# IrrigationControl.net
KiCad netlist of a schematic drawn in EAGLE
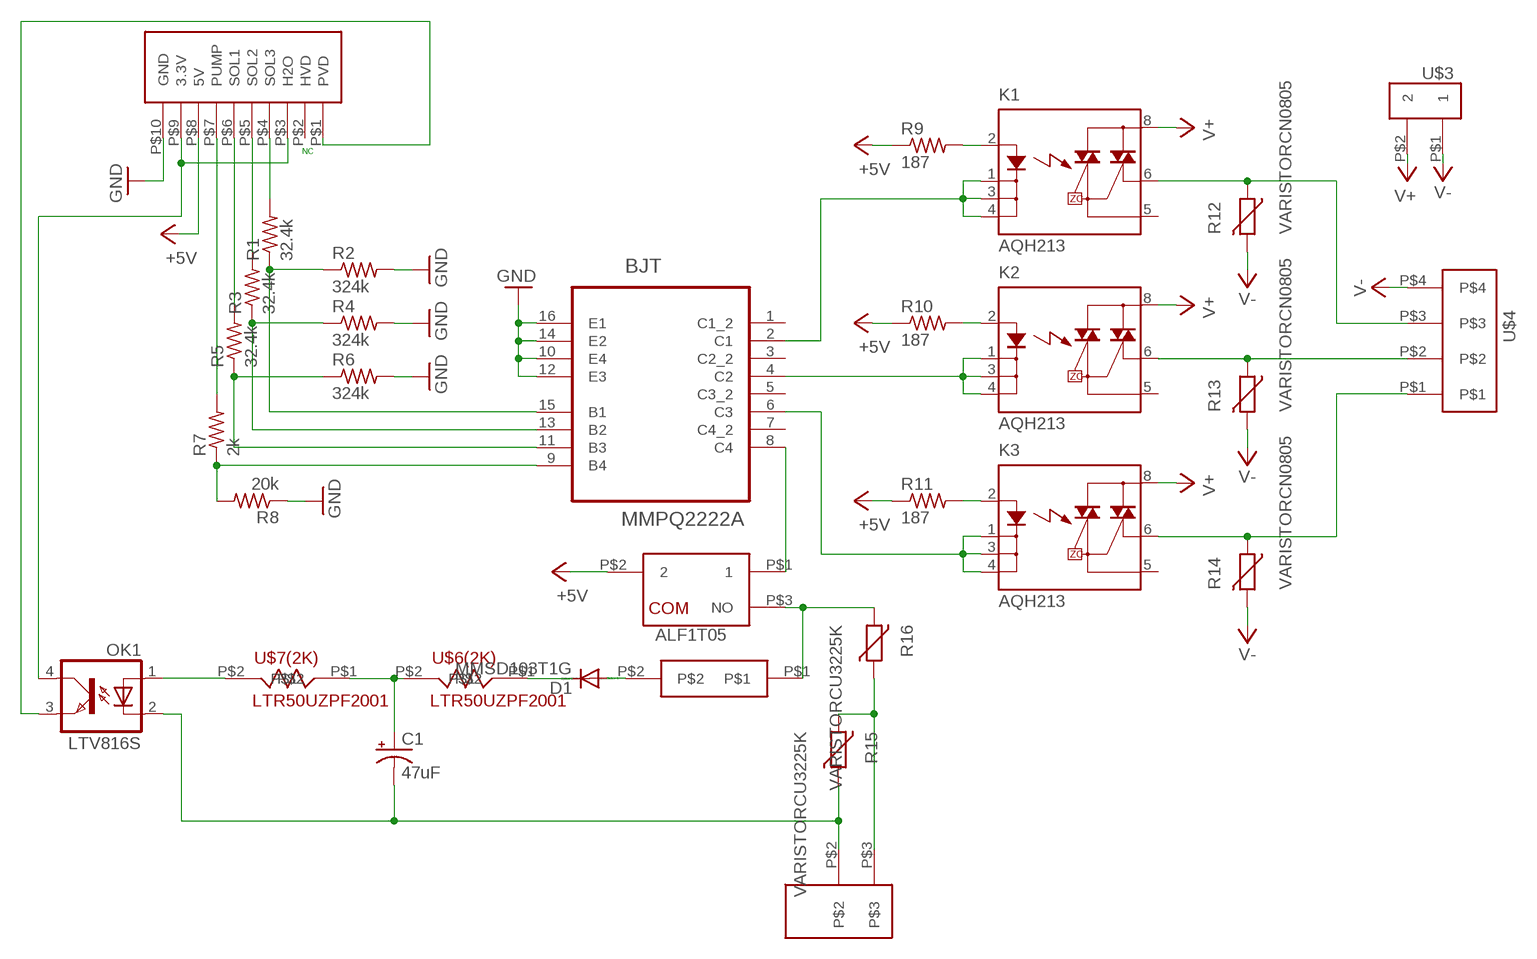
[diagram p0: schematic, sheet 1]

(export (version "E")
  (design (tool "Eeschema 10.0.6"))
  (components
    (comp (ref "ALF1T05")
      (value "ALF1T05")
      (footprint "eagle-import:TMP")
      (libsource (lib "eagle-import") (part "ALF1T05"))
    )
    (comp (ref "BJT")
      (value "MMPQ2222A")
      (footprint "eagle-import:SOIC127P600X175-16N")
      (libsource (lib "eagle-import") (part "MMPQ2222A"))
    )
    (comp (ref "C1")
      (value "47uF")
      (footprint "eagle-import:E5-10,5")
      (libsource (lib "eagle-import") (part "CPOL-USE5-10.5"))
    )
    (comp (ref "D1")
      (value "MMSD103T1G")
      (footprint "eagle-import:SOD123")
      (libsource (lib "eagle-import") (part "DIODE-SOD123"))
    )
    (comp (ref "K1")
      (value "AQH213")
      (footprint "eagle-import:DIL07")
      (libsource (lib "eagle-import") (part "AQH213"))
    )
    (comp (ref "K2")
      (value "AQH213")
      (footprint "eagle-import:DIL07")
      (libsource (lib "eagle-import") (part "AQH213"))
    )
    (comp (ref "K3")
      (value "AQH213")
      (footprint "eagle-import:DIL07")
      (libsource (lib "eagle-import") (part "AQH213"))
    )
    (comp (ref "OK1")
      (value "LTV816S")
      (footprint "eagle-import:SMD4")
      (libsource (lib "eagle-import") (part "LTV816S"))
    )
    (comp (ref "R1")
      (value "32.4k")
      (footprint "eagle-import:R0805")
      (libsource (lib "eagle-import") (part "R-US_R0805"))
    )
    (comp (ref "R2")
      (value "324k")
      (footprint "eagle-import:R0805")
      (libsource (lib "eagle-import") (part "R-US_R0805"))
    )
    (comp (ref "R3")
      (value "32.4k")
      (footprint "eagle-import:R0805")
      (libsource (lib "eagle-import") (part "R-US_R0805"))
    )
    (comp (ref "R4")
      (value "324k")
      (footprint "eagle-import:R0805")
      (libsource (lib "eagle-import") (part "R-US_R0805"))
    )
    (comp (ref "R5")
      (value "32.4k")
      (footprint "eagle-import:R0805")
      (libsource (lib "eagle-import") (part "R-US_R0805"))
    )
    (comp (ref "R6")
      (value "324k")
      (footprint "eagle-import:R0805")
      (libsource (lib "eagle-import") (part "R-US_R0805"))
    )
    (comp (ref "R7")
      (value "2k")
      (footprint "eagle-import:R0805")
      (libsource (lib "eagle-import") (part "R-US_R0805"))
    )
    (comp (ref "R8")
      (value "20k")
      (footprint "eagle-import:R0805")
      (libsource (lib "eagle-import") (part "R-US_R0805"))
    )
    (comp (ref "R9")
      (value "187")
      (footprint "eagle-import:R0805")
      (libsource (lib "eagle-import") (part "R-US_R0805"))
    )
    (comp (ref "R10")
      (value "187")
      (footprint "eagle-import:R0805")
      (libsource (lib "eagle-import") (part "R-US_R0805"))
    )
    (comp (ref "R11")
      (value "187")
      (footprint "eagle-import:R0805")
      (libsource (lib "eagle-import") (part "R-US_R0805"))
    )
    (comp (ref "R12")
      (value "VARISTORCN0805")
      (footprint "eagle-import:CT_CN0805")
      (libsource (lib "eagle-import") (part "VARISTORCN0805"))
    )
    (comp (ref "R13")
      (value "VARISTORCN0805")
      (footprint "eagle-import:CT_CN0805")
      (libsource (lib "eagle-import") (part "VARISTORCN0805"))
    )
    (comp (ref "R14")
      (value "VARISTORCN0805")
      (footprint "eagle-import:CT_CN0805")
      (libsource (lib "eagle-import") (part "VARISTORCN0805"))
    )
    (comp (ref "R15")
      (value "VARISTORCU3225K")
      (footprint "eagle-import:CU3225K")
      (libsource (lib "eagle-import") (part "VARISTORCU3225K"))
    )
    (comp (ref "R16")
      (value "VARISTORCU3225K")
      (footprint "eagle-import:CU3225K")
      (libsource (lib "eagle-import") (part "VARISTORCU3225K"))
    )
    (comp (ref "U$1")
      (value "OSTT7030150")
      (footprint "eagle-import:OSTT7030150")
      (libsource (lib "eagle-import") (part "OSTT7030150"))
    )
    (comp (ref "U$2")
      (value "OSTTE100104")
      (footprint "eagle-import:OSTTE100104")
      (libsource (lib "eagle-import") (part "OSTTE100104"))
    )
    (comp (ref "U$3")
      (value "OSTTC020162")
      (footprint "eagle-import:OSTTC020162")
      (libsource (lib "eagle-import") (part "OSTTC020162"))
    )
    (comp (ref "U$4")
      (value "OSTTE040104")
      (footprint "eagle-import:OSTTEX040104")
      (libsource (lib "eagle-import") (part "OSTTE040104"))
    )
    (comp (ref "U$5")
      (value "SST-357")
      (footprint "eagle-import:SST")
      (libsource (lib "eagle-import") (part "SST-357"))
    )
    (comp (ref "U$6(2K)")
      (value "LTR50UZPF2001")
      (footprint "eagle-import:WIDE2010")
      (libsource (lib "eagle-import") (part "LTR50UZPF2001"))
    )
    (comp (ref "U$7(2K)")
      (value "LTR50UZPF2001")
      (footprint "eagle-import:WIDE2010")
      (libsource (lib "eagle-import") (part "LTR50UZPF2001"))
    )
  )
  (nets
    (net (code "1") (name "+5V") (class "Default")
      (node (ref "ALF1T05") (pin "P$2") (pinfunction "2_P$2") (pintype "bidirectional"))
      (node (ref "R10") (pin "1") (pinfunction "1_1") (pintype "passive"))
      (node (ref "R11") (pin "1") (pinfunction "1_1") (pintype "passive"))
      (node (ref "R9") (pin "1") (pinfunction "1_1") (pintype "passive"))
      (node (ref "U$2") (pin "P$8") (pinfunction "5V_P$8") (pintype "power_in"))
    )
    (net (code "2") (name "GND") (class "Default")
      (node (ref "BJT") (pin "10") (pinfunction "E4_10") (pintype "passive"))
      (node (ref "BJT") (pin "12") (pinfunction "E3_12") (pintype "passive"))
      (node (ref "BJT") (pin "14") (pinfunction "E2_14") (pintype "passive"))
      (node (ref "BJT") (pin "16") (pinfunction "E1_16") (pintype "passive"))
      (node (ref "R2") (pin "2") (pinfunction "2_2") (pintype "passive"))
      (node (ref "R4") (pin "2") (pinfunction "2_2") (pintype "passive"))
      (node (ref "R6") (pin "2") (pinfunction "2_2") (pintype "passive"))
      (node (ref "R8") (pin "1") (pinfunction "1_1") (pintype "passive"))
      (node (ref "U$2") (pin "P$10") (pinfunction "GND_P$10") (pintype "bidirectional"))
    )
    (net (code "3") (name "Net-(ALF1T05-1)") (class "Default")
      (node (ref "ALF1T05") (pin "P$1") (pinfunction "1_P$1") (pintype "bidirectional"))
      (node (ref "BJT") (pin "8") (pinfunction "C4_8") (pintype "passive"))
    )
    (net (code "4") (name "Net-(ALF1T05-NO)") (class "Default")
      (node (ref "ALF1T05") (pin "P$3") (pinfunction "NO_P$3") (pintype "bidirectional"))
      (node (ref "R16") (pin "2") (pinfunction "2_2") (pintype "passive"))
      (node (ref "U$5") (pin "P$1") (pinfunction "P$1_P$1") (pintype "bidirectional"))
    )
    (net (code "5") (name "Net-(BJT-B1)") (class "Default")
      (node (ref "BJT") (pin "15") (pinfunction "B1_15") (pintype "passive"))
      (node (ref "R1") (pin "1") (pinfunction "1_1") (pintype "passive"))
      (node (ref "R2") (pin "1") (pinfunction "1_1") (pintype "passive"))
    )
    (net (code "6") (name "Net-(BJT-B2)") (class "Default")
      (node (ref "BJT") (pin "13") (pinfunction "B2_13") (pintype "passive"))
      (node (ref "R3") (pin "1") (pinfunction "1_1") (pintype "passive"))
      (node (ref "R4") (pin "1") (pinfunction "1_1") (pintype "passive"))
    )
    (net (code "7") (name "Net-(BJT-B3)") (class "Default")
      (node (ref "BJT") (pin "11") (pinfunction "B3_11") (pintype "passive"))
      (node (ref "R5") (pin "1") (pinfunction "1_1") (pintype "passive"))
      (node (ref "R6") (pin "1") (pinfunction "1_1") (pintype "passive"))
    )
    (net (code "8") (name "Net-(BJT-B4)") (class "Default")
      (node (ref "BJT") (pin "9") (pinfunction "B4_9") (pintype "passive"))
      (node (ref "R7") (pin "1") (pinfunction "1_1") (pintype "passive"))
      (node (ref "R8") (pin "2") (pinfunction "2_2") (pintype "passive"))
    )
    (net (code "9") (name "Net-(BJT-C1)") (class "Default")
      (node (ref "BJT") (pin "2") (pinfunction "C1_2") (pintype "passive"))
      (node (ref "K1") (pin "1") (pinfunction "K_1") (pintype "passive"))
      (node (ref "K1") (pin "3") (pinfunction "K1_3") (pintype "passive"))
      (node (ref "K1") (pin "4") (pinfunction "K2_4") (pintype "passive"))
    )
    (net (code "10") (name "Net-(BJT-C2)") (class "Default")
      (node (ref "BJT") (pin "4") (pinfunction "C2_4") (pintype "passive"))
      (node (ref "K2") (pin "1") (pinfunction "K_1") (pintype "passive"))
      (node (ref "K2") (pin "3") (pinfunction "K1_3") (pintype "passive"))
      (node (ref "K2") (pin "4") (pinfunction "K2_4") (pintype "passive"))
    )
    (net (code "11") (name "Net-(BJT-C3)") (class "Default")
      (node (ref "BJT") (pin "6") (pinfunction "C3_6") (pintype "passive"))
      (node (ref "K3") (pin "1") (pinfunction "K_1") (pintype "passive"))
      (node (ref "K3") (pin "3") (pinfunction "K1_3") (pintype "passive"))
      (node (ref "K3") (pin "4") (pinfunction "K2_4") (pintype "passive"))
    )
    (net (code "12") (name "Net-(C1-Pad+)") (class "Default")
      (node (ref "C1") (pin "+") (pinfunction "+_+") (pintype "passive"))
      (node (ref "U$6(2K)") (pin "P$2") (pinfunction "P$2_P$2") (pintype "bidirectional"))
      (node (ref "U$7(2K)") (pin "P$1") (pinfunction "P$1_P$1") (pintype "bidirectional"))
    )
    (net (code "13") (name "Net-(D1-PadA)") (class "Default")
      (node (ref "D1") (pin "A") (pinfunction "A_A") (pintype "passive"))
      (node (ref "U$5") (pin "P$2") (pinfunction "P$2_P$2") (pintype "bidirectional"))
    )
    (net (code "14") (name "Net-(D1-PadC)") (class "Default")
      (node (ref "D1") (pin "C") (pinfunction "C_C") (pintype "passive"))
      (node (ref "U$6(2K)") (pin "P$1") (pinfunction "P$1_P$1") (pintype "bidirectional"))
    )
    (net (code "15") (name "Net-(K1-A)") (class "Default")
      (node (ref "K1") (pin "2") (pinfunction "A_2") (pintype "passive"))
      (node (ref "R9") (pin "2") (pinfunction "2_2") (pintype "passive"))
    )
    (net (code "16") (name "Net-(K1-DS3)") (class "Default")
      (node (ref "K1") (pin "6") (pinfunction "DS3_6") (pintype "passive"))
      (node (ref "R12") (pin "1") (pinfunction "1_1") (pintype "passive"))
      (node (ref "U$4") (pin "P$3") (pinfunction "P$3_P$3") (pintype "bidirectional"))
    )
    (net (code "17") (name "Net-(K2-A)") (class "Default")
      (node (ref "K2") (pin "2") (pinfunction "A_2") (pintype "passive"))
      (node (ref "R10") (pin "2") (pinfunction "2_2") (pintype "passive"))
    )
    (net (code "18") (name "Net-(K2-DS3)") (class "Default")
      (node (ref "K2") (pin "6") (pinfunction "DS3_6") (pintype "passive"))
      (node (ref "R13") (pin "1") (pinfunction "1_1") (pintype "passive"))
      (node (ref "U$4") (pin "P$2") (pinfunction "P$2_P$2") (pintype "bidirectional"))
    )
    (net (code "19") (name "Net-(K3-A)") (class "Default")
      (node (ref "K3") (pin "2") (pinfunction "A_2") (pintype "passive"))
      (node (ref "R11") (pin "2") (pinfunction "2_2") (pintype "passive"))
    )
    (net (code "20") (name "Net-(K3-DS3)") (class "Default")
      (node (ref "K3") (pin "6") (pinfunction "DS3_6") (pintype "passive"))
      (node (ref "R14") (pin "1") (pinfunction "1_1") (pintype "passive"))
      (node (ref "U$4") (pin "P$1") (pinfunction "P$1_P$1") (pintype "bidirectional"))
    )
    (net (code "21") (name "Net-(OK1-A)") (class "Default")
      (node (ref "OK1") (pin "1") (pinfunction "A_1") (pintype "passive"))
      (node (ref "U$7(2K)") (pin "P$2") (pinfunction "P$2_P$2") (pintype "bidirectional"))
    )
    (net (code "22") (name "Net-(OK1-C)") (class "Default")
      (node (ref "C1") (pin "-") (pinfunction "-_-") (pintype "passive"))
      (node (ref "OK1") (pin "2") (pinfunction "C_2") (pintype "passive"))
      (node (ref "R15") (pin "1") (pinfunction "1_1") (pintype "passive"))
      (node (ref "U$1") (pin "P$2") (pinfunction "P$2_P$2") (pintype "bidirectional"))
    )
    (net (code "23") (name "Net-(OK1-COL)") (class "Default")
      (node (ref "OK1") (pin "4") (pinfunction "COL_4") (pintype "passive"))
      (node (ref "U$2") (pin "P$3") (pinfunction "H2O_P$3") (pintype "power_in"))
      (node (ref "U$2") (pin "P$9") (pinfunction "3.3V_P$9") (pintype "power_in"))
    )
    (net (code "24") (name "Net-(OK1-EMIT)") (class "Default")
      (node (ref "OK1") (pin "3") (pinfunction "EMIT_3") (pintype "passive"))
      (node (ref "U$2") (pin "P$1") (pinfunction "PVD_P$1") (pintype "input"))
    )
    (net (code "25") (name "Net-(R15-Pad2)") (class "Default")
      (node (ref "R15") (pin "2") (pinfunction "2_2") (pintype "passive"))
      (node (ref "R16") (pin "1") (pinfunction "1_1") (pintype "passive"))
      (node (ref "U$1") (pin "P$3") (pinfunction "P$3_P$3") (pintype "bidirectional"))
    )
    (net (code "26") (name "Net-(U$2-PUMP)") (class "Default")
      (node (ref "R7") (pin "2") (pinfunction "2_2") (pintype "passive"))
      (node (ref "U$2") (pin "P$7") (pinfunction "PUMP_P$7") (pintype "output"))
    )
    (net (code "27") (name "Net-(U$2-SOL1)") (class "Default")
      (node (ref "R5") (pin "2") (pinfunction "2_2") (pintype "passive"))
      (node (ref "U$2") (pin "P$6") (pinfunction "SOL1_P$6") (pintype "output"))
    )
    (net (code "28") (name "Net-(U$2-SOL2)") (class "Default")
      (node (ref "R3") (pin "2") (pinfunction "2_2") (pintype "passive"))
      (node (ref "U$2") (pin "P$5") (pinfunction "SOL2_P$5") (pintype "output"))
    )
    (net (code "29") (name "Net-(U$2-SOL3)") (class "Default")
      (node (ref "R1") (pin "2") (pinfunction "2_2") (pintype "passive"))
      (node (ref "U$2") (pin "P$4") (pinfunction "SOL3_P$4") (pintype "output"))
    )
    (net (code "30") (name "V+") (class "Default")
      (node (ref "K1") (pin "8") (pinfunction "DS1_8") (pintype "passive"))
      (node (ref "K2") (pin "8") (pinfunction "DS1_8") (pintype "passive"))
      (node (ref "K3") (pin "8") (pinfunction "DS1_8") (pintype "passive"))
      (node (ref "U$3") (pin "P$2") (pinfunction "2_P$2") (pintype "bidirectional"))
    )
    (net (code "31") (name "V-") (class "Default")
      (node (ref "R12") (pin "2") (pinfunction "2_2") (pintype "passive"))
      (node (ref "R13") (pin "2") (pinfunction "2_2") (pintype "passive"))
      (node (ref "R14") (pin "2") (pinfunction "2_2") (pintype "passive"))
      (node (ref "U$3") (pin "P$1") (pinfunction "1_P$1") (pintype "bidirectional"))
      (node (ref "U$4") (pin "P$4") (pinfunction "P$4_P$4") (pintype "bidirectional"))
    )
    (net (code "32") (name "unconnected-(BJT-C1_2-Pad1)") (class "Default")
      (node (ref "BJT") (pin "1") (pinfunction "C1_2_1") (pintype "passive"))
    )
    (net (code "33") (name "unconnected-(BJT-C2_2-Pad3)") (class "Default")
      (node (ref "BJT") (pin "3") (pinfunction "C2_2_3") (pintype "passive"))
    )
    (net (code "34") (name "unconnected-(BJT-C3_2-Pad5)") (class "Default")
      (node (ref "BJT") (pin "5") (pinfunction "C3_2_5") (pintype "passive"))
    )
    (net (code "35") (name "unconnected-(BJT-C4_2-Pad7)") (class "Default")
      (node (ref "BJT") (pin "7") (pinfunction "C4_2_7") (pintype "passive"))
    )
    (net (code "36") (name "unconnected-(K1-DS2-Pad5)") (class "Default")
      (node (ref "K1") (pin "5") (pinfunction "DS2_5") (pintype "passive"))
    )
    (net (code "37") (name "unconnected-(K2-DS2-Pad5)") (class "Default")
      (node (ref "K2") (pin "5") (pinfunction "DS2_5") (pintype "passive"))
    )
    (net (code "38") (name "unconnected-(K3-DS2-Pad5)") (class "Default")
      (node (ref "K3") (pin "5") (pinfunction "DS2_5") (pintype "passive"))
    )
    (net (code "39") (name "unconnected-(U$2-HVD-PadP$2)") (class "Default")
      (node (ref "U$2") (pin "P$2") (pinfunction "HVD_P$2") (pintype "bidirectional"))
    )
  )
)
